# DM2097_EEPROM.net
KiCad netlist of a schematic drawn in Altium Designer
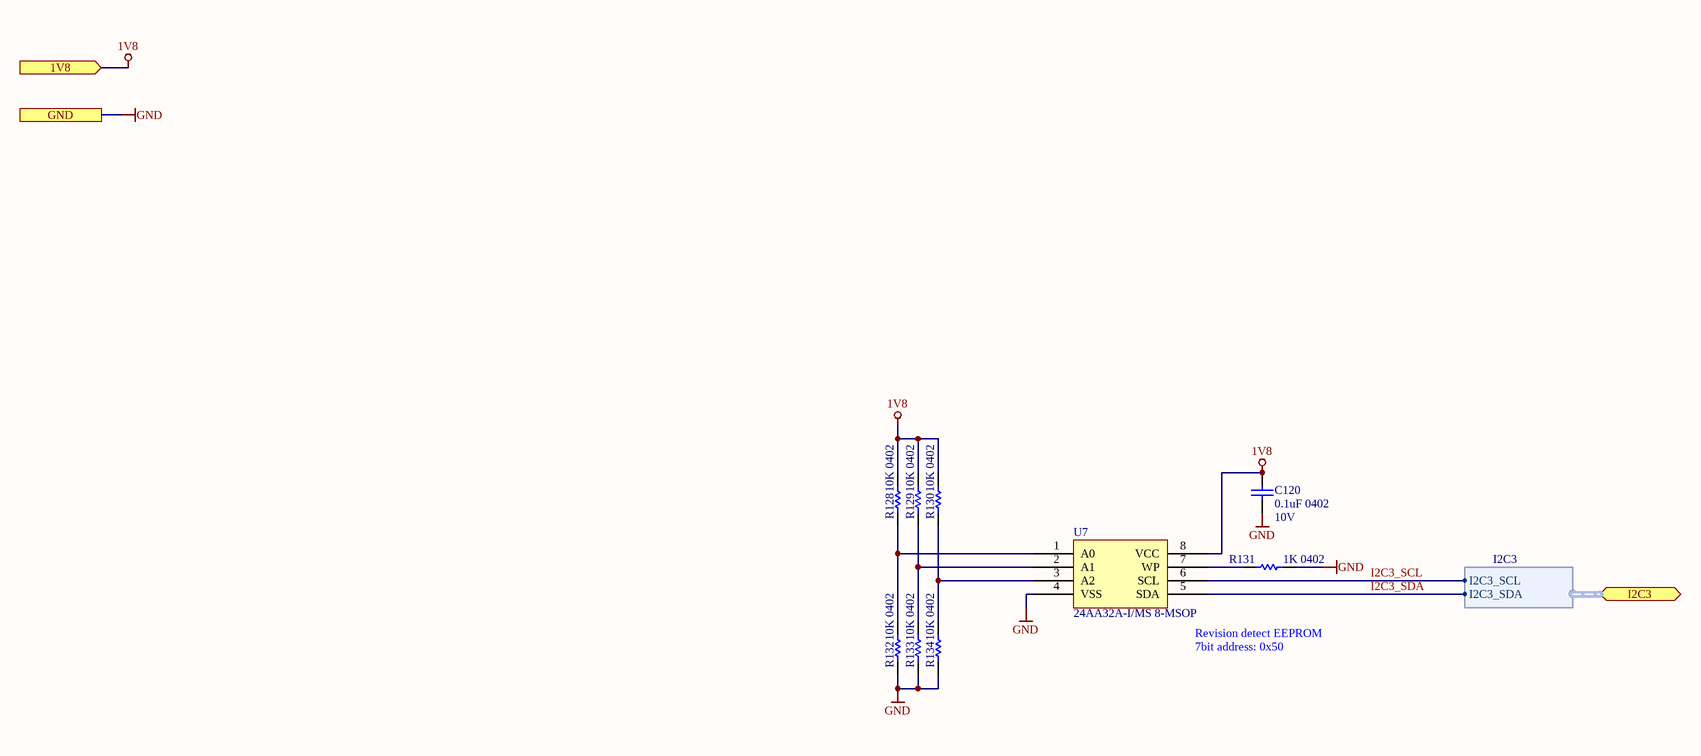
[diagram p0: DM2097_EEPROM.SchDoc]

(export (version "E")
  (design (tool "Eeschema 10.0.6"))
  (components
    (comp (ref "C120")
      (value "0.1uF 0402")
      (footprint "CAP_Altium_Vault_Generic:CAPC0402(1005)70_L")
      (description "CAP CER 0.1UF 10V X7R 0402 5%")
      (fields (field (name "TOLERANCE") "5%") (field (name "VOLTAGE RATING") "10V"))
      (libsource (lib "LuxonisMaster") (part "GRM155R71A104JA01D"))
    )
    (comp (ref "R128")
      (value "10K 0402")
      (footprint "RES_Altium_Vault_Generic:RESC0402(1005)_L")
      (fields (field (name "TOLERANCE") "1%"))
      (libsource (lib "LuxonisMaster") (part "RC0402FR-1310KL"))
    )
    (comp (ref "R129")
      (value "10K 0402")
      (footprint "RES_Altium_Vault_Generic:RESC0402(1005)_L")
      (fields (field (name "TOLERANCE") "1%"))
      (libsource (lib "LuxonisMaster") (part "RC0402FR-1310KL"))
    )
    (comp (ref "R130")
      (value "10K 0402")
      (footprint "RES_Altium_Vault_Generic:RESC0402(1005)_L")
      (fields (field (name "TOLERANCE") "1%"))
      (libsource (lib "LuxonisMaster") (part "RC0402FR-1310KL"))
    )
    (comp (ref "R131")
      (value "1K 0402")
      (footprint "RES_Altium_Vault_Generic:RESC0402(1005)_L")
      (description "RES SMD 1K OHM 1% 1/16W 0402")
      (fields (field (name "TOLERANCE") "1%"))
      (libsource (lib "LuxonisMaster") (part "RC0402FR-071KL"))
    )
    (comp (ref "R132")
      (value "10K 0402")
      (footprint "RES_Altium_Vault_Generic:RESC0402(1005)_L")
      (fields (field (name "TOLERANCE") "1%"))
      (libsource (lib "LuxonisMaster") (part "RC0402FR-1310KL"))
    )
    (comp (ref "R133")
      (value "10K 0402")
      (footprint "RES_Altium_Vault_Generic:RESC0402(1005)_L")
      (fields (field (name "TOLERANCE") "1%"))
      (libsource (lib "LuxonisMaster") (part "RC0402FR-1310KL"))
    )
    (comp (ref "R134")
      (value "10K 0402")
      (footprint "RES_Altium_Vault_Generic:RESC0402(1005)_L")
      (fields (field (name "TOLERANCE") "1%"))
      (libsource (lib "LuxonisMaster") (part "RC0402FR-1310KL"))
    )
    (comp (ref "U7")
      (value "24AA32A-I/MS 8-MSOP")
      (footprint "LuxonisMaster:24AA32A-I/MS")
      (description "IC EEPROM 32K I2C 400KHZ 8MSOP Memory IC 32Kb (4K x 8) I²C 400kHz 900ns 8-MSOP")
      (libsource (lib "LuxonisMaster") (part "24AA32A-I/MS"))
    )
  )
  (nets
    (net (code "2") (name "/I2C3_SCL") (class "Default")
      (node (ref "U7") (pin "6") (pinfunction "SCL_6") (pintype "passive"))
    )
    (net (code "3") (name "/I2C3_SDA") (class "Default")
      (node (ref "U7") (pin "5") (pinfunction "SDA_5") (pintype "passive"))
    )
    (net (code "5") (name "1V8") (class "Default")
      (node (ref "C120") (pin "2") (pinfunction "2_2") (pintype "passive"))
      (node (ref "R128") (pin "2") (pinfunction "2_2") (pintype "passive"))
      (node (ref "R129") (pin "2") (pinfunction "2_2") (pintype "passive"))
      (node (ref "R130") (pin "2") (pinfunction "2_2") (pintype "passive"))
      (node (ref "U7") (pin "8") (pinfunction "VCC_8") (pintype "passive"))
    )
    (net (code "6") (name "GND") (class "Default")
      (node (ref "C120") (pin "1") (pinfunction "1_1") (pintype "passive"))
      (node (ref "R131") (pin "1") (pinfunction "1_1") (pintype "passive"))
      (node (ref "R132") (pin "1") (pinfunction "1_1") (pintype "passive"))
      (node (ref "R133") (pin "1") (pinfunction "1_1") (pintype "passive"))
      (node (ref "R134") (pin "1") (pinfunction "1_1") (pintype "passive"))
      (node (ref "U7") (pin "4") (pinfunction "VSS_4") (pintype "passive"))
    )
    (net (code "7") (name "Net-(U7-A0)") (class "Default")
      (node (ref "R128") (pin "1") (pinfunction "1_1") (pintype "passive"))
      (node (ref "R132") (pin "2") (pinfunction "2_2") (pintype "passive"))
      (node (ref "U7") (pin "1") (pinfunction "A0_1") (pintype "passive"))
    )
    (net (code "8") (name "Net-(U7-A1)") (class "Default")
      (node (ref "R129") (pin "1") (pinfunction "1_1") (pintype "passive"))
      (node (ref "R133") (pin "2") (pinfunction "2_2") (pintype "passive"))
      (node (ref "U7") (pin "2") (pinfunction "A1_2") (pintype "passive"))
    )
    (net (code "9") (name "Net-(U7-A2)") (class "Default")
      (node (ref "R130") (pin "1") (pinfunction "1_1") (pintype "passive"))
      (node (ref "R134") (pin "2") (pinfunction "2_2") (pintype "passive"))
      (node (ref "U7") (pin "3") (pinfunction "A2_3") (pintype "passive"))
    )
    (net (code "10") (name "Net-(U7-WP)") (class "Default")
      (node (ref "R131") (pin "2") (pinfunction "2_2") (pintype "passive"))
      (node (ref "U7") (pin "7") (pinfunction "WP_7") (pintype "passive"))
    )
  )
)
